# Regulators.net
KiCad netlist of a schematic drawn in Altium Designer
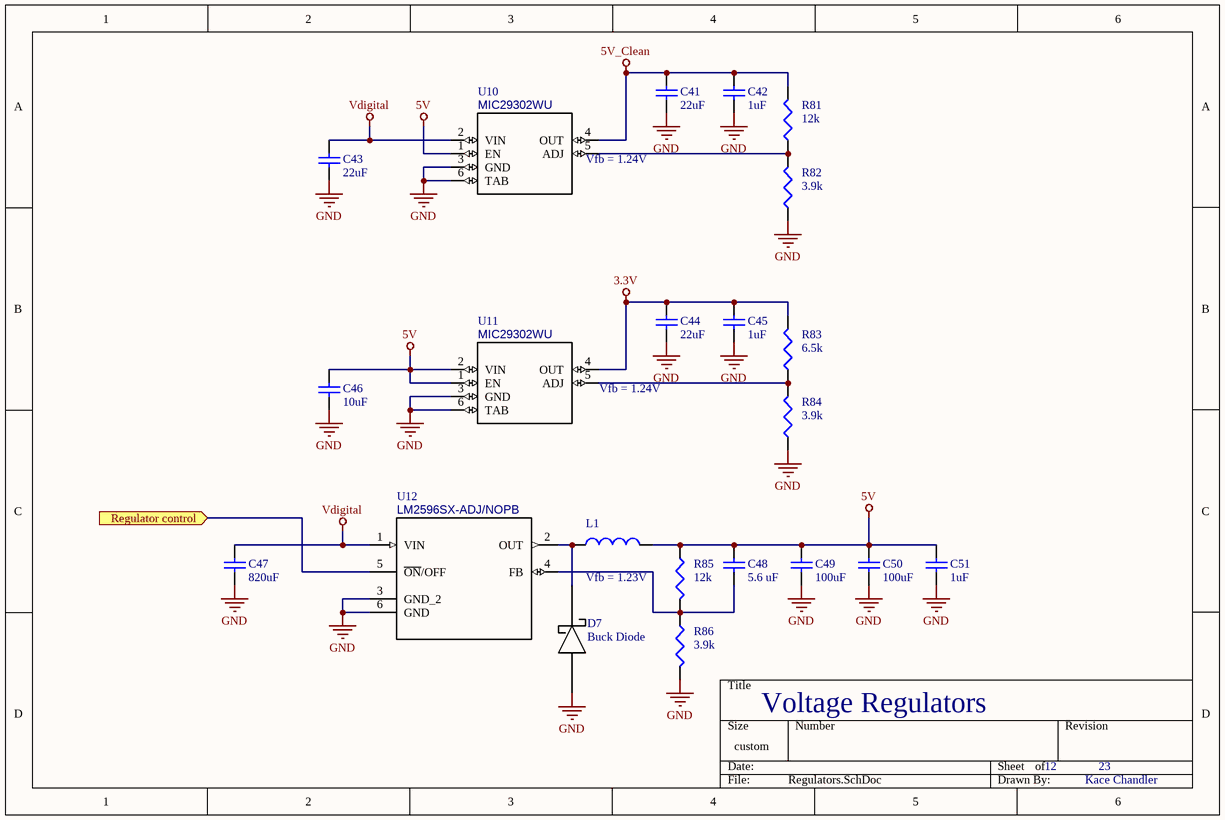
[diagram p0: Regulators.SchDoc]

(export (version "E")
  (design (tool "Eeschema 10.0.6"))
  (components
    (comp (ref "C41")
      (value "22uF")
      (footprint "0603 to 1210 SMD")
      (description "Capacitor")
      (fields (field (name "Comment") "Cap") (field (name "PUBLISHER") "Altium Limited"))
      (libsource (lib "Miscellaneous Devices") (part "Cap"))
    )
    (comp (ref "C42")
      (value "1uF")
      (footprint "0603 to 0805 SMD")
      (description "Capacitor")
      (fields (field (name "Comment") "Cap") (field (name "PUBLISHER") "Altium Limited"))
      (libsource (lib "Miscellaneous Devices") (part "Cap"))
    )
    (comp (ref "C43")
      (value "22uF")
      (footprint "0603 to 1210 SMD")
      (description "Capacitor")
      (fields (field (name "Comment") "Cap") (field (name "PUBLISHER") "Altium Limited"))
      (libsource (lib "Miscellaneous Devices") (part "Cap"))
    )
    (comp (ref "C44")
      (value "22uF")
      (footprint "0603 to 1210 SMD")
      (description "Capacitor")
      (fields (field (name "Comment") "Cap") (field (name "PUBLISHER") "Altium Limited"))
      (libsource (lib "Miscellaneous Devices") (part "Cap"))
    )
    (comp (ref "C45")
      (value "1uF")
      (footprint "0603 to 0805 SMD")
      (description "Capacitor")
      (fields (field (name "Comment") "Cap") (field (name "PUBLISHER") "Altium Limited"))
      (libsource (lib "Miscellaneous Devices") (part "Cap"))
    )
    (comp (ref "C46")
      (value "10uF")
      (footprint "0805 Footprint")
      (description "Capacitor")
      (fields (field (name "Comment") "Cap") (field (name "PUBLISHER") "Altium Limited"))
      (libsource (lib "Miscellaneous Devices") (part "Cap"))
    )
    (comp (ref "C47")
      (value "820uF")
      (footprint "Electrolytic Cap")
      (description "Capacitor")
      (fields (field (name "Comment") "Cap") (field (name "PUBLISHER") "Altium Limited"))
      (libsource (lib "Miscellaneous Devices") (part "Cap"))
    )
    (comp (ref "C48")
      (value "5.6 uF")
      (footprint "0603 to 1210 SMD")
      (description "Capacitor")
      (fields (field (name "Comment") "Cap") (field (name "PUBLISHER") "Altium Limited"))
      (libsource (lib "Miscellaneous Devices") (part "Cap"))
    )
    (comp (ref "C49")
      (value "100uF")
      (footprint "0603 to 1210 SMD")
      (description "Capacitor")
      (fields (field (name "Comment") "Cap") (field (name "PUBLISHER") "Altium Limited"))
      (libsource (lib "Miscellaneous Devices") (part "Cap"))
    )
    (comp (ref "C50")
      (value "100uF")
      (footprint "0603 to 1210 SMD")
      (description "Capacitor")
      (fields (field (name "Comment") "Cap") (field (name "PUBLISHER") "Altium Limited"))
      (libsource (lib "Miscellaneous Devices") (part "Cap"))
    )
    (comp (ref "C51")
      (value "1uF")
      (footprint "0603 to 0805 SMD")
      (description "Capacitor")
      (fields (field (name "Comment") "Cap") (field (name "PUBLISHER") "Altium Limited"))
      (libsource (lib "Miscellaneous Devices") (part "Cap"))
    )
    (comp (ref "D7")
      (value "Buck Diode")
      (footprint "*DO-214AC")
      (libsource (lib "AvionicsParts") (part "Buck Diode"))
    )
    (comp (ref "L1")
      (value "7447709330")
      (footprint "INDUCTOR")
      (description "Inductor, SMD [WÃ¼rth Elektronik] 7447709330 Inductor, SMD")
      (fields (field (name "MF") "Wurth Electronics"))
      (libsource (lib "AvionicsParts") (part "Buck Inductor"))
    )
    (comp (ref "R81")
      (value "12k")
      (description "Resistor")
      (fields (field (name "Comment") "Res3") (field (name "PUBLISHER") "Altium Limited"))
      (libsource (lib "Miscellaneous Devices") (part "Res3"))
    )
    (comp (ref "R82")
      (value "3.9k")
      (description "Resistor")
      (fields (field (name "Comment") "Res3") (field (name "PUBLISHER") "Altium Limited"))
      (libsource (lib "Miscellaneous Devices") (part "Res3"))
    )
    (comp (ref "R83")
      (value "6.5k")
      (description "Resistor")
      (fields (field (name "Comment") "Res3") (field (name "PUBLISHER") "Altium Limited"))
      (libsource (lib "Miscellaneous Devices") (part "Res3"))
    )
    (comp (ref "R84")
      (value "3.9k")
      (description "Resistor")
      (fields (field (name "Comment") "Res3") (field (name "PUBLISHER") "Altium Limited"))
      (libsource (lib "Miscellaneous Devices") (part "Res3"))
    )
    (comp (ref "R85")
      (value "12k")
      (description "Resistor")
      (fields (field (name "Comment") "Res3") (field (name "PUBLISHER") "Altium Limited"))
      (libsource (lib "Miscellaneous Devices") (part "Res3"))
    )
    (comp (ref "R86")
      (value "3.9k")
      (description "Resistor")
      (fields (field (name "Comment") "Res3") (field (name "PUBLISHER") "Altium Limited"))
      (libsource (lib "Miscellaneous Devices") (part "Res3"))
    )
    (comp (ref "U10")
      (value "Linear Regulator")
      (footprint "*TO170P1435X465-6N")
      (description "MIC29302 Series 3 A 1.24 to 26 V ADJ Output Voltage LDO Regulator - TO-263-5")
      (fields (field (name "MP") "MIC29302WU") (field (name "MF") "Microchip"))
      (libsource (lib "AvionicsParts") (part "Linear Regulator"))
    )
    (comp (ref "U11")
      (value "Linear Regulator")
      (footprint "*TO170P1435X465-6N")
      (description "MIC29302 Series 3 A 1.24 to 26 V ADJ Output Voltage LDO Regulator - TO-263-5")
      (fields (field (name "MP") "MIC29302WU") (field (name "MF") "Microchip"))
      (libsource (lib "AvionicsParts") (part "Linear Regulator"))
    )
    (comp (ref "U12")
      (value "LM2596SX-ADJ/NOPB")
      (footprint "*TO170P1435X465-6N")
      (description "SIMPLE SWITCHERÂ® 4.5V to 40V, 3A Low Component Count Step-Down Regulator 5-DDPAK/TO-263 -40 to 125")
      (fields (field (name "MP") "LM2596SX-ADJ/NOPB") (field (name "MF") "Texas Instruments"))
      (libsource (lib "AvionicsParts") (part "Switching Regulator ADJ"))
    )
  )
  (nets
    (net (code "1") (name "/Regulator control") (class "Default")
      (node (ref "U12") (pin "5") (pinfunction "~{ON}/OFF_5") (pintype "passive"))
    )
    (net (code "2") (name "3.3V") (class "Default")
      (node (ref "C44") (pin "2") (pinfunction "2_2") (pintype "passive"))
      (node (ref "C45") (pin "2") (pinfunction "2_2") (pintype "passive"))
      (node (ref "R83") (pin "2") (pinfunction "2_2") (pintype "passive"))
      (node (ref "U11") (pin "4") (pinfunction "OUT_4") (pintype "bidirectional"))
    )
    (net (code "3") (name "5V") (class "Default")
      (node (ref "C46") (pin "2") (pinfunction "2_2") (pintype "passive"))
      (node (ref "C48") (pin "2") (pinfunction "2_2") (pintype "passive"))
      (node (ref "C49") (pin "2") (pinfunction "2_2") (pintype "passive"))
      (node (ref "C50") (pin "2") (pinfunction "2_2") (pintype "passive"))
      (node (ref "C51") (pin "2") (pinfunction "2_2") (pintype "passive"))
      (node (ref "L1") (pin "2") (pinfunction "2_2") (pintype "passive"))
      (node (ref "R85") (pin "1") (pinfunction "1_1") (pintype "passive"))
      (node (ref "U10") (pin "1") (pinfunction "EN_1") (pintype "bidirectional"))
      (node (ref "U11") (pin "1") (pinfunction "EN_1") (pintype "bidirectional"))
      (node (ref "U11") (pin "2") (pinfunction "VIN_2") (pintype "bidirectional"))
    )
    (net (code "4") (name "5V_Clean") (class "Default")
      (node (ref "C41") (pin "2") (pinfunction "2_2") (pintype "passive"))
      (node (ref "C42") (pin "2") (pinfunction "2_2") (pintype "passive"))
      (node (ref "R81") (pin "2") (pinfunction "2_2") (pintype "passive"))
      (node (ref "U10") (pin "4") (pinfunction "OUT_4") (pintype "bidirectional"))
    )
    (net (code "5") (name "GND") (class "Default")
      (node (ref "C41") (pin "1") (pinfunction "1_1") (pintype "passive"))
      (node (ref "C42") (pin "1") (pinfunction "1_1") (pintype "passive"))
      (node (ref "C43") (pin "1") (pinfunction "1_1") (pintype "passive"))
      (node (ref "C44") (pin "1") (pinfunction "1_1") (pintype "passive"))
      (node (ref "C45") (pin "1") (pinfunction "1_1") (pintype "passive"))
      (node (ref "C46") (pin "1") (pinfunction "1_1") (pintype "passive"))
      (node (ref "C47") (pin "1") (pinfunction "1_1") (pintype "passive"))
      (node (ref "C49") (pin "1") (pinfunction "1_1") (pintype "passive"))
      (node (ref "C50") (pin "1") (pinfunction "1_1") (pintype "passive"))
      (node (ref "C51") (pin "1") (pinfunction "1_1") (pintype "passive"))
      (node (ref "D7") (pin "1") (pinfunction "A_1") (pintype "passive"))
      (node (ref "R82") (pin "1") (pinfunction "1_1") (pintype "passive"))
      (node (ref "R84") (pin "1") (pinfunction "1_1") (pintype "passive"))
      (node (ref "R86") (pin "2") (pinfunction "2_2") (pintype "passive"))
      (node (ref "U10") (pin "3") (pinfunction "GND_3") (pintype "bidirectional"))
      (node (ref "U10") (pin "6") (pinfunction "TAB_6") (pintype "bidirectional"))
      (node (ref "U11") (pin "3") (pinfunction "GND_3") (pintype "bidirectional"))
      (node (ref "U11") (pin "6") (pinfunction "TAB_6") (pintype "bidirectional"))
      (node (ref "U12") (pin "3") (pinfunction "GND_2_3") (pintype "passive"))
      (node (ref "U12") (pin "6") (pinfunction "GND_6") (pintype "passive"))
    )
    (net (code "6") (name "Net-(D7-C)") (class "Default")
      (node (ref "D7") (pin "2") (pinfunction "C_2") (pintype "passive"))
      (node (ref "L1") (pin "1") (pinfunction "1_1") (pintype "passive"))
      (node (ref "U12") (pin "2") (pinfunction "OUT_2") (pintype "output"))
    )
    (net (code "7") (name "Net-(U10-ADJ)") (class "Default")
      (node (ref "R81") (pin "1") (pinfunction "1_1") (pintype "passive"))
      (node (ref "R82") (pin "2") (pinfunction "2_2") (pintype "passive"))
      (node (ref "U10") (pin "5") (pinfunction "ADJ_5") (pintype "bidirectional"))
    )
    (net (code "8") (name "Net-(U11-ADJ)") (class "Default")
      (node (ref "R83") (pin "1") (pinfunction "1_1") (pintype "passive"))
      (node (ref "R84") (pin "2") (pinfunction "2_2") (pintype "passive"))
      (node (ref "U11") (pin "5") (pinfunction "ADJ_5") (pintype "bidirectional"))
    )
    (net (code "9") (name "Net-(U12-FB)") (class "Default")
      (node (ref "C48") (pin "1") (pinfunction "1_1") (pintype "passive"))
      (node (ref "R85") (pin "2") (pinfunction "2_2") (pintype "passive"))
      (node (ref "R86") (pin "1") (pinfunction "1_1") (pintype "passive"))
      (node (ref "U12") (pin "4") (pinfunction "FB_4") (pintype "bidirectional"))
    )
    (net (code "10") (name "Vdigital") (class "Default")
      (node (ref "C43") (pin "2") (pinfunction "2_2") (pintype "passive"))
      (node (ref "C47") (pin "2") (pinfunction "2_2") (pintype "passive"))
      (node (ref "U10") (pin "2") (pinfunction "VIN_2") (pintype "bidirectional"))
      (node (ref "U12") (pin "1") (pinfunction "VIN_1") (pintype "input"))
    )
  )
)
